# Channels.net
KiCad netlist of a schematic drawn in Altium Designer
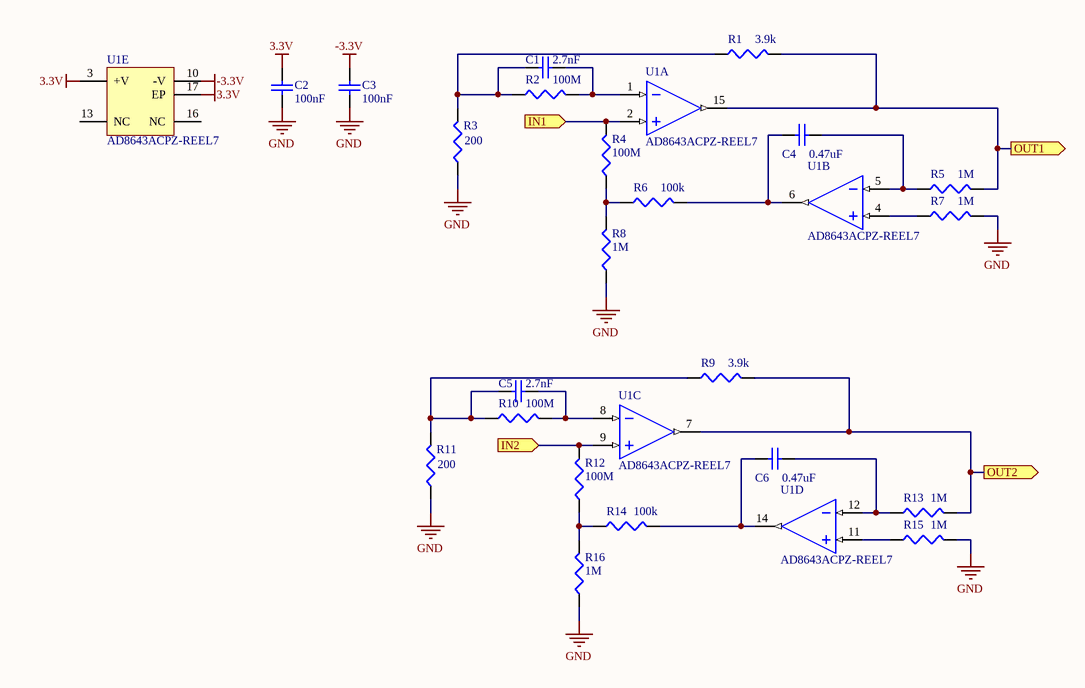
[diagram p0: Channels.SchDoc]

(export (version "E")
  (design (tool "Eeschema 10.0.6"))
  (components
    (comp (ref "C1")
      (value "2.7nF")
      (footprint "0201")
      (description "Capacitor (Semiconductor SIM Model)")
      (fields (field (name "Comment") "Cap Semi") (field (name "PUBLISHER") "Altium Limited"))
      (libsource (lib "Miscellaneous Devices") (part "Cap Semi"))
    )
    (comp (ref "C2")
      (value "100nF")
      (footprint "0201")
      (description "Capacitor (Semiconductor SIM Model)")
      (fields (field (name "Comment") "Cap Semi") (field (name "PUBLISHER") "Altium Limited"))
      (libsource (lib "Miscellaneous Devices") (part "Cap Semi"))
    )
    (comp (ref "C3")
      (value "100nF")
      (footprint "0201")
      (description "Capacitor (Semiconductor SIM Model)")
      (fields (field (name "Comment") "Cap Semi") (field (name "PUBLISHER") "Altium Limited"))
      (libsource (lib "Miscellaneous Devices") (part "Cap Semi"))
    )
    (comp (ref "C4")
      (value "0.47uF")
      (footprint "0402")
      (description "Capacitor (Semiconductor SIM Model)")
      (fields (field (name "Comment") "Cap Semi") (field (name "PUBLISHER") "Altium Limited"))
      (libsource (lib "Miscellaneous Devices") (part "Cap Semi"))
    )
    (comp (ref "C5")
      (value "2.7nF")
      (footprint "0201")
      (description "Capacitor (Semiconductor SIM Model)")
      (fields (field (name "Comment") "Cap Semi") (field (name "PUBLISHER") "Altium Limited"))
      (libsource (lib "Miscellaneous Devices") (part "Cap Semi"))
    )
    (comp (ref "C6")
      (value "0.47uF")
      (footprint "0402")
      (description "Capacitor (Semiconductor SIM Model)")
      (fields (field (name "Comment") "Cap Semi") (field (name "PUBLISHER") "Altium Limited"))
      (libsource (lib "Miscellaneous Devices") (part "Cap Semi"))
    )
    (comp (ref "R1")
      (value "3.9k")
      (footprint "01005")
      (description "Resistor")
      (fields (field (name "Comment") "Res3") (field (name "PUBLISHER") "Altium Limited"))
      (libsource (lib "Miscellaneous Devices") (part "Res3"))
    )
    (comp (ref "R2")
      (value "100M")
      (footprint "01005")
      (description "Resistor")
      (fields (field (name "Comment") "Res3") (field (name "PUBLISHER") "Altium Limited"))
      (libsource (lib "Miscellaneous Devices") (part "Res3"))
    )
    (comp (ref "R3")
      (value "200")
      (footprint "01005")
      (description "Resistor")
      (fields (field (name "Comment") "Res3") (field (name "PUBLISHER") "Altium Limited"))
      (libsource (lib "Miscellaneous Devices") (part "Res3"))
    )
    (comp (ref "R4")
      (value "100M")
      (footprint "0402")
      (description "Resistor")
      (fields (field (name "Comment") "Res3") (field (name "PUBLISHER") "Altium Limited"))
      (libsource (lib "Miscellaneous Devices") (part "Res3"))
    )
    (comp (ref "R5")
      (value "1M")
      (footprint "01005")
      (description "Resistor")
      (fields (field (name "Comment") "Res3") (field (name "PUBLISHER") "Altium Limited"))
      (libsource (lib "Miscellaneous Devices") (part "Res3"))
    )
    (comp (ref "R6")
      (value "100k")
      (footprint "01005")
      (description "Resistor")
      (fields (field (name "Comment") "Res3") (field (name "PUBLISHER") "Altium Limited"))
      (libsource (lib "Miscellaneous Devices") (part "Res3"))
    )
    (comp (ref "R7")
      (value "1M")
      (footprint "01005")
      (description "Resistor")
      (fields (field (name "Comment") "Res3") (field (name "PUBLISHER") "Altium Limited"))
      (libsource (lib "Miscellaneous Devices") (part "Res3"))
    )
    (comp (ref "R8")
      (value "1M")
      (footprint "01005")
      (description "Resistor")
      (fields (field (name "Comment") "Res3") (field (name "PUBLISHER") "Altium Limited"))
      (libsource (lib "Miscellaneous Devices") (part "Res3"))
    )
    (comp (ref "R9")
      (value "3.9k")
      (footprint "01005")
      (description "Resistor")
      (fields (field (name "Comment") "Res3") (field (name "PUBLISHER") "Altium Limited"))
      (libsource (lib "Miscellaneous Devices") (part "Res3"))
    )
    (comp (ref "R10")
      (value "100M")
      (footprint "01005")
      (description "Resistor")
      (fields (field (name "Comment") "Res3") (field (name "PUBLISHER") "Altium Limited"))
      (libsource (lib "Miscellaneous Devices") (part "Res3"))
    )
    (comp (ref "R11")
      (value "200")
      (footprint "01005")
      (description "Resistor")
      (fields (field (name "Comment") "Res3") (field (name "PUBLISHER") "Altium Limited"))
      (libsource (lib "Miscellaneous Devices") (part "Res3"))
    )
    (comp (ref "R12")
      (value "100M")
      (footprint "0402")
      (description "Resistor")
      (fields (field (name "Comment") "Res3") (field (name "PUBLISHER") "Altium Limited"))
      (libsource (lib "Miscellaneous Devices") (part "Res3"))
    )
    (comp (ref "R13")
      (value "1M")
      (footprint "01005")
      (description "Resistor")
      (fields (field (name "Comment") "Res3") (field (name "PUBLISHER") "Altium Limited"))
      (libsource (lib "Miscellaneous Devices") (part "Res3"))
    )
    (comp (ref "R14")
      (value "100k")
      (footprint "01005")
      (description "Resistor")
      (fields (field (name "Comment") "Res3") (field (name "PUBLISHER") "Altium Limited"))
      (libsource (lib "Miscellaneous Devices") (part "Res3"))
    )
    (comp (ref "R15")
      (value "1M")
      (footprint "01005")
      (description "Resistor")
      (fields (field (name "Comment") "Res3") (field (name "PUBLISHER") "Altium Limited"))
      (libsource (lib "Miscellaneous Devices") (part "Res3"))
    )
    (comp (ref "R16")
      (value "1M")
      (footprint "01005")
      (description "Resistor")
      (fields (field (name "Comment") "Res3") (field (name "PUBLISHER") "Altium Limited"))
      (libsource (lib "Miscellaneous Devices") (part "Res3"))
    )
    (comp (ref "U1")
      (value "AD8643ACPZ-REEL7")
      (footprint "ADI-CP-16-3_N")
      (fields (field (name "GENERIC PART NUMBER") "AD8643") (field (name "MANUFACTURER") "Analog Devices"))
      (libsource (lib "") (part "AD8643ACPZ-REEL7_1"))
    )
  )
  (nets
    (net (code "1") (name "-3.3V") (class "Default")
      (node (ref "C3") (pin "2") (pinfunction "2_2") (pintype "passive"))
      (node (ref "U1") (pin "10") (pinfunction "-V_10") (pintype "power_in"))
    )
    (net (code "2") (name "/IN1") (class "Default")
      (node (ref "R4") (pin "2") (pinfunction "2_2") (pintype "passive"))
      (node (ref "U1") (pin "2") (pinfunction "+IN_A_2") (pintype "input"))
    )
    (net (code "3") (name "/IN2") (class "Default")
      (node (ref "R12") (pin "2") (pinfunction "2_2") (pintype "passive"))
      (node (ref "U1") (pin "9") (pinfunction "+IN_C_9") (pintype "input"))
    )
    (net (code "4") (name "/OUT1") (class "Default")
      (node (ref "R1") (pin "2") (pinfunction "2_2") (pintype "passive"))
      (node (ref "R5") (pin "2") (pinfunction "2_2") (pintype "passive"))
      (node (ref "U1") (pin "15") (pinfunction "OUT_A_15") (pintype "output"))
    )
    (net (code "5") (name "/OUT2") (class "Default")
      (node (ref "R13") (pin "2") (pinfunction "2_2") (pintype "passive"))
      (node (ref "R9") (pin "2") (pinfunction "2_2") (pintype "passive"))
      (node (ref "U1") (pin "7") (pinfunction "OUT_C_7") (pintype "output"))
    )
    (net (code "6") (name "3.3V") (class "Default")
      (node (ref "C2") (pin "2") (pinfunction "2_2") (pintype "passive"))
      (node (ref "U1") (pin "17") (pinfunction "EP_17") (pintype "power_in"))
      (node (ref "U1") (pin "3") (pinfunction "+V_3") (pintype "power_in"))
    )
    (net (code "7") (name "GND") (class "Default")
      (node (ref "C2") (pin "1") (pinfunction "1_1") (pintype "passive"))
      (node (ref "C3") (pin "1") (pinfunction "1_1") (pintype "passive"))
      (node (ref "R11") (pin "1") (pinfunction "1_1") (pintype "passive"))
      (node (ref "R15") (pin "2") (pinfunction "2_2") (pintype "passive"))
      (node (ref "R16") (pin "1") (pinfunction "1_1") (pintype "passive"))
      (node (ref "R3") (pin "1") (pinfunction "1_1") (pintype "passive"))
      (node (ref "R7") (pin "2") (pinfunction "2_2") (pintype "passive"))
      (node (ref "R8") (pin "1") (pinfunction "1_1") (pintype "passive"))
    )
    (net (code "8") (name "Net-(C1-Pad1)") (class "Default")
      (node (ref "C1") (pin "1") (pinfunction "1_1") (pintype "passive"))
      (node (ref "R1") (pin "1") (pinfunction "1_1") (pintype "passive"))
      (node (ref "R2") (pin "1") (pinfunction "1_1") (pintype "passive"))
      (node (ref "R3") (pin "2") (pinfunction "2_2") (pintype "passive"))
    )
    (net (code "9") (name "Net-(C5-Pad1)") (class "Default")
      (node (ref "C5") (pin "1") (pinfunction "1_1") (pintype "passive"))
      (node (ref "R10") (pin "1") (pinfunction "1_1") (pintype "passive"))
      (node (ref "R11") (pin "2") (pinfunction "2_2") (pintype "passive"))
      (node (ref "R9") (pin "1") (pinfunction "1_1") (pintype "passive"))
    )
    (net (code "10") (name "Net-(R4-Pad1)") (class "Default")
      (node (ref "R4") (pin "1") (pinfunction "1_1") (pintype "passive"))
      (node (ref "R6") (pin "1") (pinfunction "1_1") (pintype "passive"))
      (node (ref "R8") (pin "2") (pinfunction "2_2") (pintype "passive"))
    )
    (net (code "11") (name "Net-(R12-Pad1)") (class "Default")
      (node (ref "R12") (pin "1") (pinfunction "1_1") (pintype "passive"))
      (node (ref "R14") (pin "1") (pinfunction "1_1") (pintype "passive"))
      (node (ref "R16") (pin "2") (pinfunction "2_2") (pintype "passive"))
    )
    (net (code "12") (name "Net-(U1A--IN_A)") (class "Default")
      (node (ref "C1") (pin "2") (pinfunction "2_2") (pintype "passive"))
      (node (ref "R2") (pin "2") (pinfunction "2_2") (pintype "passive"))
      (node (ref "U1") (pin "1") (pinfunction "-IN_A_1") (pintype "input"))
    )
    (net (code "13") (name "Net-(U1B-+IN_B)") (class "Default")
      (node (ref "R7") (pin "1") (pinfunction "1_1") (pintype "passive"))
      (node (ref "U1") (pin "4") (pinfunction "+IN_B_4") (pintype "input"))
    )
    (net (code "14") (name "Net-(U1B--IN_B)") (class "Default")
      (node (ref "C4") (pin "2") (pinfunction "2_2") (pintype "passive"))
      (node (ref "R5") (pin "1") (pinfunction "1_1") (pintype "passive"))
      (node (ref "U1") (pin "5") (pinfunction "-IN_B_5") (pintype "input"))
    )
    (net (code "15") (name "Net-(U1B-OUT_B)") (class "Default")
      (node (ref "C4") (pin "1") (pinfunction "1_1") (pintype "passive"))
      (node (ref "R6") (pin "2") (pinfunction "2_2") (pintype "passive"))
      (node (ref "U1") (pin "6") (pinfunction "OUT_B_6") (pintype "output"))
    )
    (net (code "16") (name "Net-(U1C--IN_C)") (class "Default")
      (node (ref "C5") (pin "2") (pinfunction "2_2") (pintype "passive"))
      (node (ref "R10") (pin "2") (pinfunction "2_2") (pintype "passive"))
      (node (ref "U1") (pin "8") (pinfunction "-IN_C_8") (pintype "input"))
    )
    (net (code "17") (name "Net-(U1D-+IN_D)") (class "Default")
      (node (ref "R15") (pin "1") (pinfunction "1_1") (pintype "passive"))
      (node (ref "U1") (pin "11") (pinfunction "+IN_D_11") (pintype "input"))
    )
    (net (code "18") (name "Net-(U1D--IN_D)") (class "Default")
      (node (ref "C6") (pin "2") (pinfunction "2_2") (pintype "passive"))
      (node (ref "R13") (pin "1") (pinfunction "1_1") (pintype "passive"))
      (node (ref "U1") (pin "12") (pinfunction "-IN_D_12") (pintype "input"))
    )
    (net (code "19") (name "Net-(U1D-OUT_D)") (class "Default")
      (node (ref "C6") (pin "1") (pinfunction "1_1") (pintype "passive"))
      (node (ref "R14") (pin "2") (pinfunction "2_2") (pintype "passive"))
      (node (ref "U1") (pin "14") (pinfunction "OUT_D_14") (pintype "output"))
    )
    (net (code "20") (name "unconnected-(U1E-NC-Pad13)") (class "Default")
      (node (ref "U1") (pin "13") (pinfunction "NC_13") (pintype "passive"))
    )
    (net (code "21") (name "unconnected-(U1E-NC-Pad16)") (class "Default")
      (node (ref "U1") (pin "16") (pinfunction "NC_16") (pintype "passive"))
    )
  )
)
